# CAN.net
KiCad netlist of a schematic drawn in Altium Designer
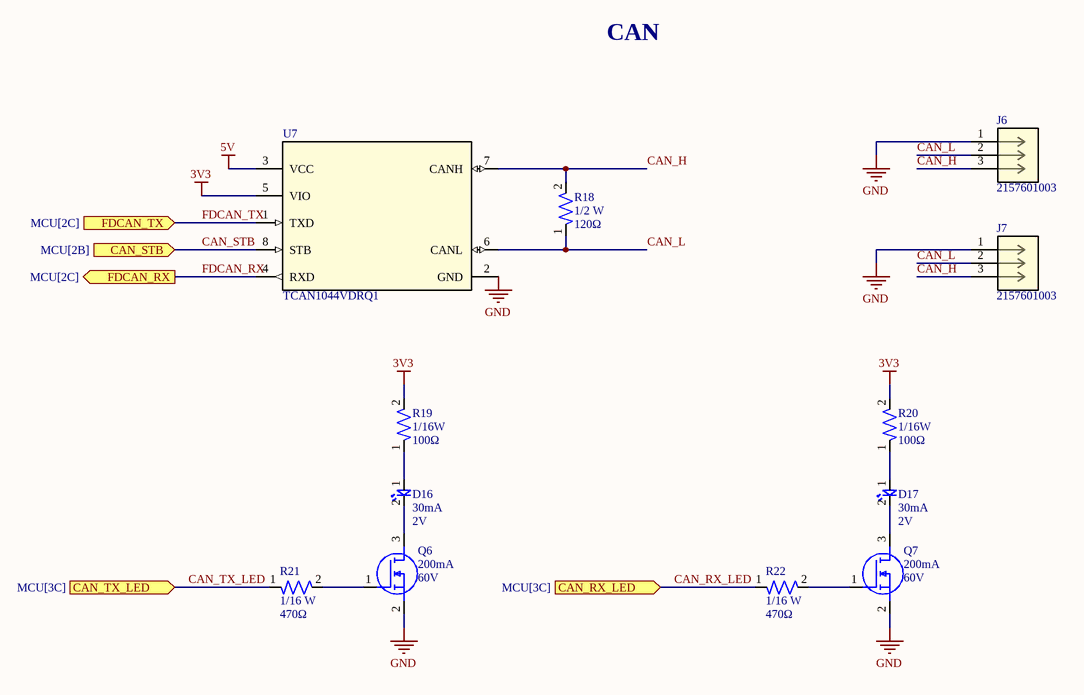
[diagram p0: CAN.SchDoc]

(export (version "E")
  (design (tool "Eeschema 10.0.6"))
  (components
    (comp (ref "D16")
      (value "BL-HKC36G-AV-TRB")
      (footprint "LED-0603")
      (description "LED YELLOW CLEAR 0603 SMD")
      (fields (field (name "FORWARD CURRENT") "30mA") (field (name "FORWARD VOLTAGE") "2V"))
      (libsource (lib "EHW_27") (part "LED-0001"))
    )
    (comp (ref "D17")
      (value "BL-HKC36G-AV-TRB")
      (footprint "LED-0603")
      (description "LED YELLOW CLEAR 0603 SMD")
      (fields (field (name "FORWARD CURRENT") "30mA") (field (name "FORWARD VOLTAGE") "2V"))
      (libsource (lib "EHW_27") (part "LED-0001"))
    )
    (comp (ref "J6")
      (value "2157601003")
      (footprint "CONN_2157600003-SD_03_PEG_MOL")
      (fields (field (name "COPYRIGHT") "Copyright (C) 2026 Ultra Librarian. All rights reserved."))
      (libsource (lib "EHW_27") (part "CONN MF+ 3 PIN Right Angle"))
    )
    (comp (ref "J7")
      (value "2157601003")
      (footprint "CONN_2157600003-SD_03_PEG_MOL")
      (fields (field (name "COPYRIGHT") "Copyright (C) 2026 Ultra Librarian. All rights reserved."))
      (libsource (lib "EHW_27") (part "CONN MF+ 3 PIN Right Angle"))
    )
    (comp (ref "Q6")
      (value "T2N7002AK,LM")
      (footprint "IC-SOT23-3")
      (description "MOSFET N-CH 60V 200MA SOT23")
      (fields (field (name "CONTINUOUS CURRENT") "200mA") (field (name "VOLTAGE") "60V"))
      (libsource (lib "EHW_27") (part "NMOS-200MA-0001"))
    )
    (comp (ref "Q7")
      (value "T2N7002AK,LM")
      (footprint "IC-SOT23-3")
      (description "MOSFET N-CH 60V 200MA SOT23")
      (fields (field (name "CONTINUOUS CURRENT") "200mA") (field (name "VOLTAGE") "60V"))
      (libsource (lib "EHW_27") (part "NMOS-200MA-0001"))
    )
    (comp (ref "R18")
      (value "RC1210FR-07120RL")
      (footprint "RES-1210")
      (fields (field (name "WATTAGE") "1/2 W") (field (name "RESISTANCE") "120Ω"))
      (libsource (lib "EHW_27") (part "RES CAN TERM 1210"))
    )
    (comp (ref "R19")
      (value "RES 0805")
      (footprint "RES-0805")
      (fields (field (name "WATTAGE") "1/16W") (field (name "RESISTANCE") "100Ω"))
      (libsource (lib "EHW_27") (part "RES 0805"))
    )
    (comp (ref "R20")
      (value "RES 0805")
      (footprint "RES-0805")
      (fields (field (name "WATTAGE") "1/16W") (field (name "RESISTANCE") "100Ω"))
      (libsource (lib "EHW_27") (part "RES 0805"))
    )
    (comp (ref "R21")
      (value "RES 0805")
      (footprint "RES-0805")
      (fields (field (name "WATTAGE") "1/16 W") (field (name "RESISTANCE") "470Ω"))
      (libsource (lib "EHW_27") (part "RES 0805"))
    )
    (comp (ref "R22")
      (value "RES 0805")
      (footprint "RES-0805")
      (fields (field (name "WATTAGE") "1/16 W") (field (name "RESISTANCE") "470Ω"))
      (libsource (lib "EHW_27") (part "RES 0805"))
    )
    (comp (ref "U7")
      (value "TCAN1044VDRQ1")
      (footprint "IC-8SOIC")
      (description "IC TRANSCEIVER 1/1 8SOIC")
      (libsource (lib "EHW_27") (part "IC-CAN-0001"))
    )
  )
  (nets
    (net (code "1") (name "/CAN_H") (class "Default")
      (node (ref "J6") (pin "3") (pinfunction "3_3") (pintype "passive"))
      (node (ref "J7") (pin "3") (pinfunction "3_3") (pintype "passive"))
      (node (ref "R18") (pin "2") (pinfunction "2_2") (pintype "passive"))
      (node (ref "U7") (pin "7") (pinfunction "CANH_7") (pintype "bidirectional"))
    )
    (net (code "2") (name "/CAN_L") (class "Default")
      (node (ref "J6") (pin "2") (pinfunction "2_2") (pintype "passive"))
      (node (ref "J7") (pin "2") (pinfunction "2_2") (pintype "passive"))
      (node (ref "R18") (pin "1") (pinfunction "1_1") (pintype "passive"))
      (node (ref "U7") (pin "6") (pinfunction "CANL_6") (pintype "bidirectional"))
    )
    (net (code "3") (name "/CAN_RX_LED") (class "Default")
      (node (ref "R22") (pin "1") (pinfunction "1_1") (pintype "passive"))
    )
    (net (code "4") (name "/CAN_STB") (class "Default")
      (node (ref "U7") (pin "8") (pinfunction "STB_8") (pintype "input"))
    )
    (net (code "5") (name "/CAN_TX_LED") (class "Default")
      (node (ref "R21") (pin "1") (pinfunction "1_1") (pintype "passive"))
    )
    (net (code "6") (name "/FDCAN_RX") (class "Default")
      (node (ref "U7") (pin "4") (pinfunction "RXD_4") (pintype "output"))
    )
    (net (code "7") (name "/FDCAN_TX") (class "Default")
      (node (ref "U7") (pin "1") (pinfunction "TXD_1") (pintype "input"))
    )
    (net (code "8") (name "3V3") (class "Default")
      (node (ref "R19") (pin "2") (pinfunction "2_2") (pintype "passive"))
      (node (ref "R20") (pin "2") (pinfunction "2_2") (pintype "passive"))
      (node (ref "U7") (pin "5") (pinfunction "VIO_5") (pintype "power_in"))
    )
    (net (code "9") (name "5V") (class "Default")
      (node (ref "U7") (pin "3") (pinfunction "VCC_3") (pintype "power_in"))
    )
    (net (code "10") (name "GND") (class "Default")
      (node (ref "J6") (pin "1") (pinfunction "1_1") (pintype "passive"))
      (node (ref "J7") (pin "1") (pinfunction "1_1") (pintype "passive"))
      (node (ref "Q6") (pin "2") (pinfunction "S_2") (pintype "passive"))
      (node (ref "Q7") (pin "2") (pinfunction "S_2") (pintype "passive"))
      (node (ref "U7") (pin "2") (pinfunction "GND_2") (pintype "power_in"))
    )
    (net (code "11") (name "Net-(D16-Pad1)") (class "Default")
      (node (ref "D16") (pin "1") (pinfunction "1_1") (pintype "passive"))
      (node (ref "R19") (pin "1") (pinfunction "1_1") (pintype "passive"))
    )
    (net (code "12") (name "Net-(D17-Pad1)") (class "Default")
      (node (ref "D17") (pin "1") (pinfunction "1_1") (pintype "passive"))
      (node (ref "R20") (pin "1") (pinfunction "1_1") (pintype "passive"))
    )
    (net (code "13") (name "Net-(Q6-D)") (class "Default")
      (node (ref "D16") (pin "2") (pinfunction "2_2") (pintype "passive"))
      (node (ref "Q6") (pin "3") (pinfunction "D_3") (pintype "passive"))
    )
    (net (code "14") (name "Net-(Q6-G)") (class "Default")
      (node (ref "Q6") (pin "1") (pinfunction "G_1") (pintype "passive"))
      (node (ref "R21") (pin "2") (pinfunction "2_2") (pintype "passive"))
    )
    (net (code "15") (name "Net-(Q7-D)") (class "Default")
      (node (ref "D17") (pin "2") (pinfunction "2_2") (pintype "passive"))
      (node (ref "Q7") (pin "3") (pinfunction "D_3") (pintype "passive"))
    )
    (net (code "16") (name "Net-(Q7-G)") (class "Default")
      (node (ref "Q7") (pin "1") (pinfunction "G_1") (pintype "passive"))
      (node (ref "R22") (pin "2") (pinfunction "2_2") (pintype "passive"))
    )
  )
)
